# SCH_SOFT-LIGHTS_1.net
KiCad netlist of a schematic drawn in EasyEDA
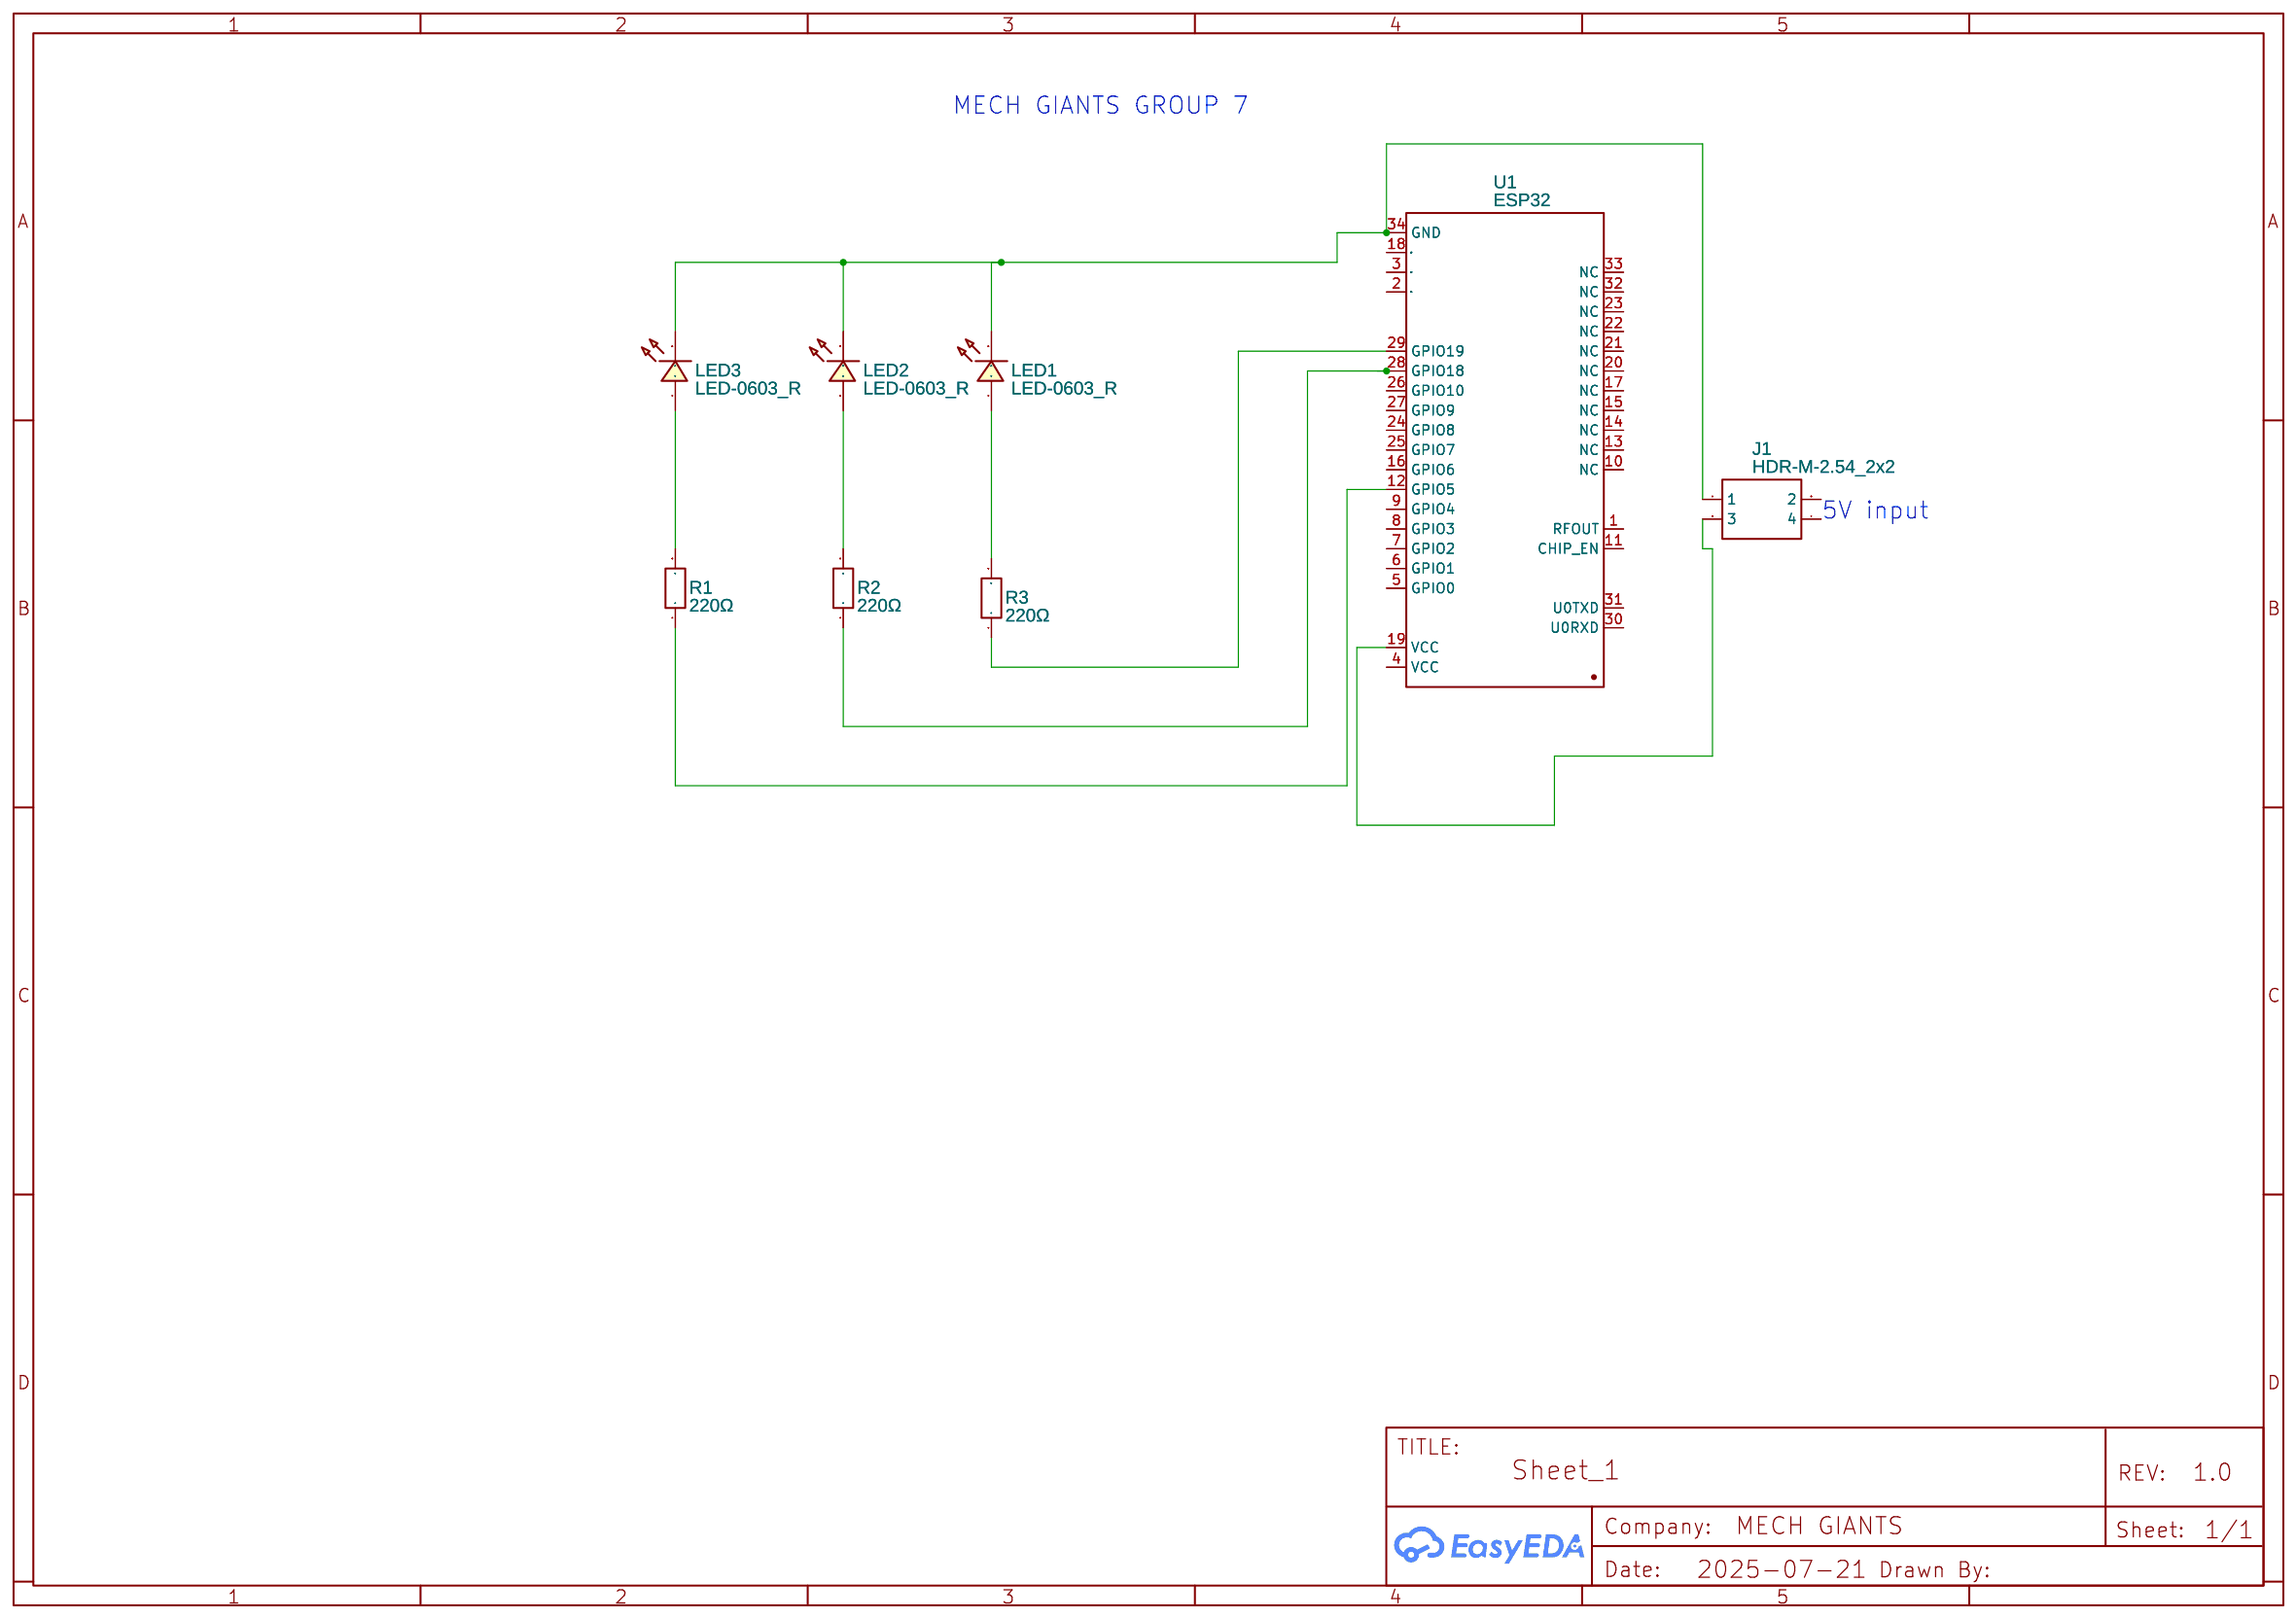
[diagram p0: schematic sheet]

(export (version "E")
  (design (tool "Eeschema 10.0.6"))
  (components
    (comp (ref "J1") (value "HDR-M-2.54_2x2") (libsource (lib "") (part "HDR-M-2.54_2x2")))
    (comp (ref "LED1")
      (value "LED-0603_R")
      (fields
        (field (name "Manufacturer Part") "19-217/R6C-AL1M2VY/3T")
        (field (name "Manufacturer") "EVERLIGHT(台湾亿光)")
      )
      (libsource (lib "") (part "LED-0603_R"))
    )
    (comp (ref "LED2")
      (value "LED-0603_R")
      (fields
        (field (name "Manufacturer Part") "19-217/R6C-AL1M2VY/3T")
        (field (name "Manufacturer") "EVERLIGHT(台湾亿光)")
      )
      (libsource (lib "") (part "LED-0603_R"))
    )
    (comp (ref "LED3")
      (value "LED-0603_R")
      (fields
        (field (name "Manufacturer Part") "19-217/R6C-AL1M2VY/3T")
        (field (name "Manufacturer") "EVERLIGHT(台湾亿光)")
      )
      (libsource (lib "") (part "LED-0603_R"))
    )
    (comp (ref "R1")
      (value "220Ω")
      (fields
        (field (name "Manufacturer Part") "MM204VF220RTKRTR3K0")
        (field (name "Manufacturer") "Firstohm(第一电阻)")
      )
      (libsource (lib "") (part "MM204VF220RTKRTR3K0"))
    )
    (comp (ref "R2")
      (value "220Ω")
      (fields
        (field (name "Manufacturer Part") "MM204VF220RTKRTR3K0")
        (field (name "Manufacturer") "Firstohm(第一电阻)")
      )
      (libsource (lib "") (part "MM204VF220RTKRTR3K0"))
    )
    (comp (ref "R3")
      (value "220Ω")
      (fields
        (field (name "Manufacturer Part") "MM204VF220RTKRTR3K0")
        (field (name "Manufacturer") "Firstohm(第一电阻)")
      )
      (libsource (lib "") (part "MM204VF220RTKRTR3K0"))
    )
    (comp (ref "U1")
      (value "ESP32")
      (fields (field (name "Manufacturer Part") "RF-WM-ESP32B1") (field (name "Manufacturer") "RF-star(信驰达)"))
      (libsource (lib "") (part "RF-WM-ESP32B1"))
    )
  )
  (nets
    (net (code "1") (name "Net-(J1-Pad1)") (class "Default")
      (node (ref "J1") (pin "1") (pinfunction "1_1") (pintype "input"))
      (node (ref "LED1") (pin "2") (pinfunction "2_2") (pintype "unspecified"))
      (node (ref "LED2") (pin "2") (pinfunction "2_2") (pintype "unspecified"))
      (node (ref "LED3") (pin "2") (pinfunction "2_2") (pintype "unspecified"))
      (node (ref "U1") (pin "34") (pinfunction "GND_34") (pintype "unspecified"))
    )
    (net (code "2") (name "Net-(J1-Pad3)") (class "Default")
      (node (ref "J1") (pin "3") (pinfunction "3_3") (pintype "input"))
      (node (ref "U1") (pin "19") (pinfunction "VCC_19") (pintype "unspecified"))
    )
    (net (code "3") (name "Net-(LED1-Pad1)") (class "Default")
      (node (ref "LED1") (pin "1") (pinfunction "1_1") (pintype "unspecified"))
      (node (ref "R3") (pin "2") (pinfunction "2_2") (pintype "unspecified"))
    )
    (net (code "4") (name "Net-(LED2-Pad1)") (class "Default")
      (node (ref "LED2") (pin "1") (pinfunction "1_1") (pintype "unspecified"))
      (node (ref "R2") (pin "2") (pinfunction "2_2") (pintype "unspecified"))
    )
    (net (code "5") (name "Net-(LED3-Pad1)") (class "Default")
      (node (ref "LED3") (pin "1") (pinfunction "1_1") (pintype "unspecified"))
      (node (ref "R1") (pin "2") (pinfunction "2_2") (pintype "unspecified"))
    )
    (net (code "6") (name "Net-(U1-GPIO5)") (class "Default")
      (node (ref "R1") (pin "1") (pinfunction "1_1") (pintype "unspecified"))
      (node (ref "U1") (pin "12") (pinfunction "GPIO5_12") (pintype "unspecified"))
    )
    (net (code "7") (name "Net-(U1-GPIO18)") (class "Default")
      (node (ref "R2") (pin "1") (pinfunction "1_1") (pintype "unspecified"))
      (node (ref "U1") (pin "28") (pinfunction "GPIO18_28") (pintype "unspecified"))
    )
    (net (code "8") (name "Net-(U1-GPIO19)") (class "Default")
      (node (ref "R3") (pin "1") (pinfunction "1_1") (pintype "unspecified"))
      (node (ref "U1") (pin "29") (pinfunction "GPIO19_29") (pintype "unspecified"))
    )
    (net (code "9") (name "unconnected-(J1-Pad2)") (class "Default")
      (node (ref "J1") (pin "2") (pinfunction "2_2") (pintype "input"))
    )
    (net (code "10") (name "unconnected-(J1-Pad4)") (class "Default")
      (node (ref "J1") (pin "4") (pinfunction "4_4") (pintype "input"))
    )
    (net (code "11") (name "unconnected-(U1-CHIP_EN-Pad11)") (class "Default")
      (node (ref "U1") (pin "11") (pinfunction "CHIP_EN_11") (pintype "unspecified"))
    )
    (net (code "12") (name "unconnected-(U1-GND-Pad2)") (class "Default")
      (node (ref "U1") (pin "2") (pinfunction "GND_2") (pintype "unspecified"))
    )
    (net (code "13") (name "unconnected-(U1-GND-Pad3)") (class "Default")
      (node (ref "U1") (pin "3") (pinfunction "GND_3") (pintype "unspecified"))
    )
    (net (code "14") (name "unconnected-(U1-GND-Pad18)") (class "Default")
      (node (ref "U1") (pin "18") (pinfunction "GND_18") (pintype "unspecified"))
    )
    (net (code "15") (name "unconnected-(U1-GPIO0-Pad5)") (class "Default")
      (node (ref "U1") (pin "5") (pinfunction "GPIO0_5") (pintype "unspecified"))
    )
    (net (code "16") (name "unconnected-(U1-GPIO1-Pad6)") (class "Default")
      (node (ref "U1") (pin "6") (pinfunction "GPIO1_6") (pintype "unspecified"))
    )
    (net (code "17") (name "unconnected-(U1-GPIO2-Pad7)") (class "Default")
      (node (ref "U1") (pin "7") (pinfunction "GPIO2_7") (pintype "unspecified"))
    )
    (net (code "18") (name "unconnected-(U1-GPIO3-Pad8)") (class "Default")
      (node (ref "U1") (pin "8") (pinfunction "GPIO3_8") (pintype "unspecified"))
    )
    (net (code "19") (name "unconnected-(U1-GPIO4-Pad9)") (class "Default")
      (node (ref "U1") (pin "9") (pinfunction "GPIO4_9") (pintype "unspecified"))
    )
    (net (code "20") (name "unconnected-(U1-GPIO6-Pad16)") (class "Default")
      (node (ref "U1") (pin "16") (pinfunction "GPIO6_16") (pintype "unspecified"))
    )
    (net (code "21") (name "unconnected-(U1-GPIO7-Pad25)") (class "Default")
      (node (ref "U1") (pin "25") (pinfunction "GPIO7_25") (pintype "unspecified"))
    )
    (net (code "22") (name "unconnected-(U1-GPIO8-Pad24)") (class "Default")
      (node (ref "U1") (pin "24") (pinfunction "GPIO8_24") (pintype "unspecified"))
    )
    (net (code "23") (name "unconnected-(U1-GPIO9-Pad27)") (class "Default")
      (node (ref "U1") (pin "27") (pinfunction "GPIO9_27") (pintype "unspecified"))
    )
    (net (code "24") (name "unconnected-(U1-GPIO10-Pad26)") (class "Default")
      (node (ref "U1") (pin "26") (pinfunction "GPIO10_26") (pintype "unspecified"))
    )
    (net (code "25") (name "unconnected-(U1-NC-Pad10)") (class "Default")
      (node (ref "U1") (pin "10") (pinfunction "NC_10") (pintype "unspecified"))
    )
    (net (code "26") (name "unconnected-(U1-NC-Pad13)") (class "Default")
      (node (ref "U1") (pin "13") (pinfunction "NC_13") (pintype "unspecified"))
    )
    (net (code "27") (name "unconnected-(U1-NC-Pad14)") (class "Default")
      (node (ref "U1") (pin "14") (pinfunction "NC_14") (pintype "unspecified"))
    )
    (net (code "28") (name "unconnected-(U1-NC-Pad15)") (class "Default")
      (node (ref "U1") (pin "15") (pinfunction "NC_15") (pintype "unspecified"))
    )
    (net (code "29") (name "unconnected-(U1-NC-Pad17)") (class "Default")
      (node (ref "U1") (pin "17") (pinfunction "NC_17") (pintype "unspecified"))
    )
    (net (code "30") (name "unconnected-(U1-NC-Pad20)") (class "Default")
      (node (ref "U1") (pin "20") (pinfunction "NC_20") (pintype "unspecified"))
    )
    (net (code "31") (name "unconnected-(U1-NC-Pad21)") (class "Default")
      (node (ref "U1") (pin "21") (pinfunction "NC_21") (pintype "unspecified"))
    )
    (net (code "32") (name "unconnected-(U1-NC-Pad22)") (class "Default")
      (node (ref "U1") (pin "22") (pinfunction "NC_22") (pintype "unspecified"))
    )
    (net (code "33") (name "unconnected-(U1-NC-Pad23)") (class "Default")
      (node (ref "U1") (pin "23") (pinfunction "NC_23") (pintype "unspecified"))
    )
    (net (code "34") (name "unconnected-(U1-NC-Pad32)") (class "Default")
      (node (ref "U1") (pin "32") (pinfunction "NC_32") (pintype "unspecified"))
    )
    (net (code "35") (name "unconnected-(U1-NC-Pad33)") (class "Default")
      (node (ref "U1") (pin "33") (pinfunction "NC_33") (pintype "unspecified"))
    )
    (net (code "36") (name "unconnected-(U1-RFOUT-Pad1)") (class "Default")
      (node (ref "U1") (pin "1") (pinfunction "RFOUT_1") (pintype "unspecified"))
    )
    (net (code "37") (name "unconnected-(U1-U0RXD-Pad30)") (class "Default")
      (node (ref "U1") (pin "30") (pinfunction "U0RXD_30") (pintype "unspecified"))
    )
    (net (code "38") (name "unconnected-(U1-U0TXD-Pad31)") (class "Default")
      (node (ref "U1") (pin "31") (pinfunction "U0TXD_31") (pintype "unspecified"))
    )
    (net (code "39") (name "unconnected-(U1-VCC-Pad4)") (class "Default")
      (node (ref "U1") (pin "4") (pinfunction "VCC_4") (pintype "unspecified"))
    )
  )
)
